# Sheet1.net
KiCad netlist of a schematic drawn in Altium Designer
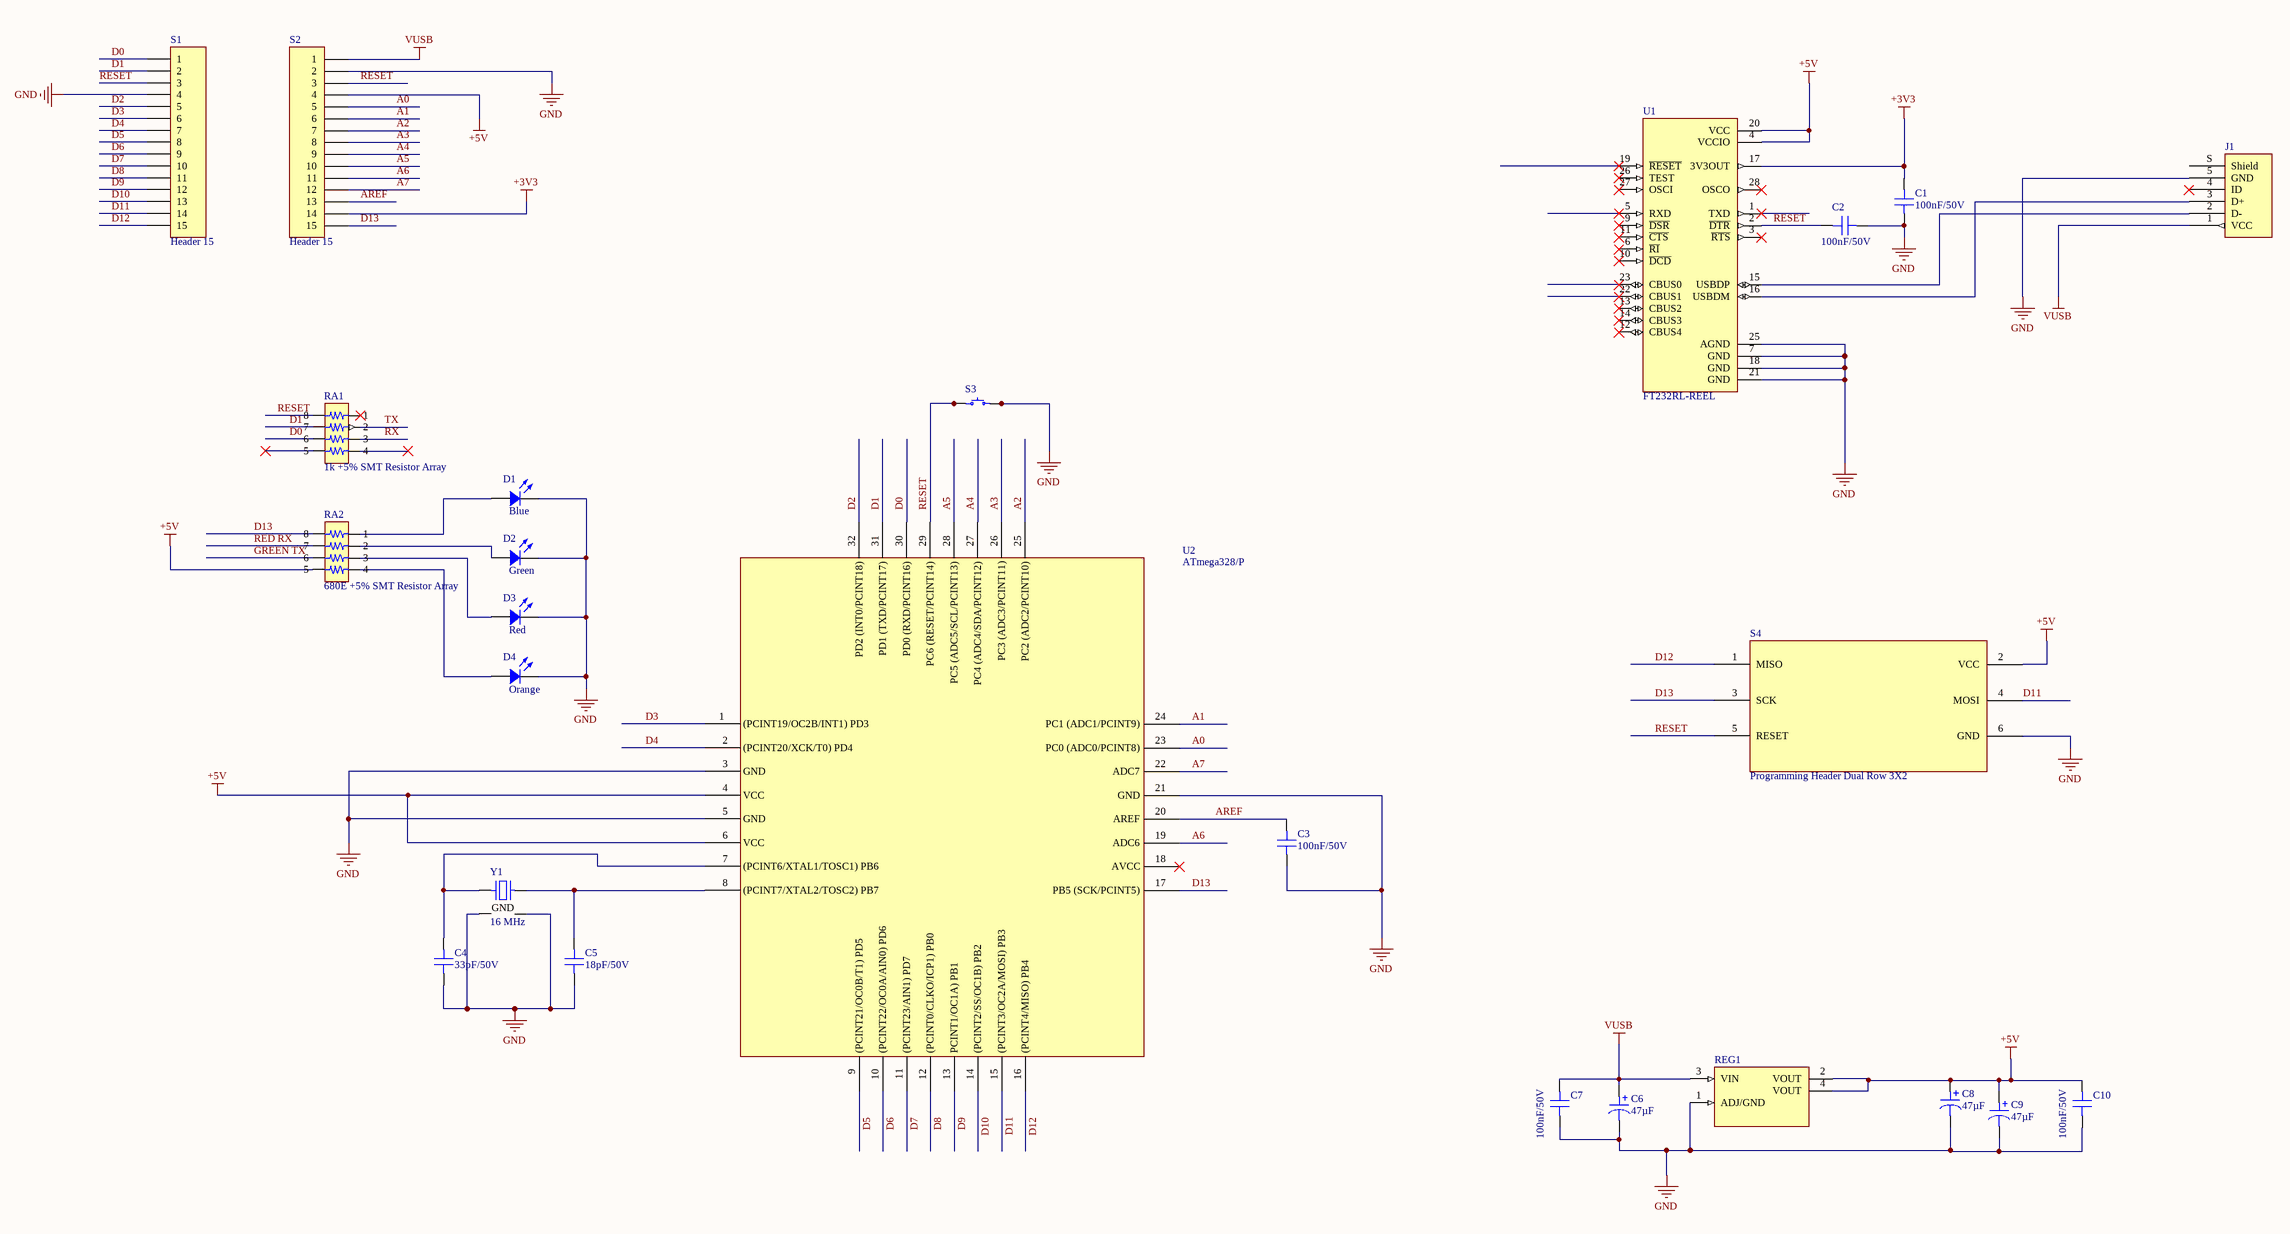
[diagram p0: Sheet1.SchDoc]

(export (version "E")
  (design (tool "Eeschema 10.0.6"))
  (components
    (comp (ref "C1")
      (value "100nF/50V")
      (footprint "CAP 0805_2012")
      (description "CAP CER 0.1UF 50V X5R 0805")
      (fields (field (name "PART NUMBER") "08055D104KAT2A") (field (name "MANUFACTURER") "AVX Corporation"))
      (libsource (lib "Celestial Altium Library - altium_library") (part "Capacitor"))
    )
    (comp (ref "C2")
      (value "100nF/50V")
      (footprint "CAP 0805_2012")
      (description "CAP CER 0.1UF 50V X5R 0805")
      (fields (field (name "PART NUMBER") "08055D104KAT2A") (field (name "MANUFACTURER") "AVX Corporation"))
      (libsource (lib "Celestial Altium Library - altium_library") (part "Capacitor"))
    )
    (comp (ref "C3")
      (value "100nF/50V")
      (footprint "CAP 0805_2012")
      (description "CAP CER 0.1UF 50V X5R 0805")
      (fields (field (name "PART NUMBER") "08055D104KAT2A") (field (name "MANUFACTURER") "AVX Corporation"))
      (libsource (lib "Celestial Altium Library - altium_library") (part "Capacitor"))
    )
    (comp (ref "C4")
      (value "33pF/50V")
      (footprint "CAP 0805_2012")
      (description "CAP CER 18PF 50V C0G/NP0 0805")
      (fields (field (name "PART NUMBER") "08055A180JAT2A") (field (name "MANUFACTURER") "AVX Corporation"))
      (libsource (lib "Celestial Altium Library - altium_library") (part "Capacitor"))
    )
    (comp (ref "C5")
      (value "18pF/50V")
      (footprint "CAP 0805_2012")
      (description "CAP CER 18PF 50V C0G/NP0 0805")
      (fields (field (name "PART NUMBER") "08055A180JAT2A") (field (name "MANUFACTURER") "AVX Corporation"))
      (libsource (lib "Celestial Altium Library - altium_library") (part "Capacitor"))
    )
    (comp (ref "C6")
      (value "47µF")
      (footprint "CAP ALSMD 8.3MM H10.5MM")
      (description "CAP ALUM 47UF 20% 63V SMD")
      (fields (field (name "PART NUMBER") "UUR1J470MNL1GS") (field (name "MANUFACTURER") "Nichicon"))
      (libsource (lib "Celestial Altium Library - altium_library") (part "Polarised Capacitor"))
    )
    (comp (ref "C7")
      (value "100nF/50V")
      (footprint "CAP 0805_2012")
      (description "CAP CER 0.1UF 50V X5R 0805")
      (fields (field (name "PART NUMBER") "08055D104KAT2A") (field (name "MANUFACTURER") "AVX Corporation"))
      (libsource (lib "Celestial Altium Library - altium_library") (part "Capacitor"))
    )
    (comp (ref "C8")
      (value "47µF")
      (footprint "CAP ALSMD 8.3MM H10.5MM")
      (description "CAP ALUM 47UF 20% 35V SMD")
      (fields (field (name "PART NUMBER") "35THV47M8X10.5") (field (name "MANUFACTURER") "Rubycon"))
      (libsource (lib "Celestial Altium Library - altium_library") (part "Polarised Capacitor"))
    )
    (comp (ref "C9")
      (value "47µF")
      (footprint "CAP ALSMD 8.3MM H10.5MM")
      (description "CAP ALUM 47UF 20% 35V SMD")
      (fields (field (name "PART NUMBER") "35THV47M8X10.5") (field (name "MANUFACTURER") "Rubycon"))
      (libsource (lib "Celestial Altium Library - altium_library") (part "Polarised Capacitor"))
    )
    (comp (ref "C10")
      (value "100nF/50V")
      (footprint "CAP 0805_2012")
      (description "CAP CER 0.1UF 50V X5R 0805")
      (fields (field (name "PART NUMBER") "08055D104KAT2A") (field (name "MANUFACTURER") "AVX Corporation"))
      (libsource (lib "Celestial Altium Library - altium_library") (part "Capacitor"))
    )
    (comp (ref "D1")
      (value "Blue")
      (footprint "LED 1206_3216 BLUE")
      (description "LED BLUE CLEAR CHIP SMD")
      (fields (field (name "PART NUMBER") "APT3216QBC/D") (field (name "MANUFACTURER") "Kingbright"))
      (libsource (lib "Celestial Altium Library - altium_library") (part "LED"))
    )
    (comp (ref "D2")
      (value "Green")
      (footprint "LED 1206_3216 GREEN")
      (description "LED GREEN 1206 SMD")
      (fields (field (name "PART NUMBER") "5976325607F") (field (name "MANUFACTURER") "Dialight"))
      (libsource (lib "Celestial Altium Library - altium_library") (part "LED"))
    )
    (comp (ref "D3")
      (value "Red")
      (footprint "LED 1206_3216 RED")
      (description "LED RED 1206 SMD")
      (fields (field (name "PART NUMBER") "5990210007F") (field (name "MANUFACTURER") "Dialight"))
      (libsource (lib "Celestial Altium Library - altium_library") (part "LED"))
    )
    (comp (ref "D4")
      (value "Orange")
      (footprint "LED 1206_3216 RED")
      (description "LED RED 1206 SMD")
      (fields (field (name "PART NUMBER") "5990210007F") (field (name "MANUFACTURER") "Dialight"))
      (libsource (lib "Celestial Altium Library - altium_library") (part "LED"))
    )
    (comp (ref "J1")
      (value "10118193-0001LF")
      (footprint "FCI USB 10118193-0001LF")
      (description "CONN RCPT USB2.0 MICRO B SMD R/A")
      (fields (field (name "MANUFACTURER") "Amphenol ICC (FCI)"))
      (libsource (lib "Celestial Altium Library - altium_library") (part "USB 2.0 Type B Micro"))
    )
    (comp (ref "RA1")
      (value "1k +5% SMT Resistor Array")
      (footprint "RESNET 1206-8 CONCAVE")
      (description "RES ARRAY 4 RES 1K OHM 1206")
      (fields (field (name "PART NUMBER") "TC164-JR-071KL") (field (name "MANUFACTURER") "Yageo"))
      (libsource (lib "Celestial Altium Library - altium_library") (part "Resistor Array (4 circuit)"))
    )
    (comp (ref "RA2")
      (value "680E +5% SMT Resistor Array")
      (footprint "RESNET 1206-8 CONVEX")
      (description "RES ARRAY 4 RES 680 OHM 1206")
      (fields (field (name "PART NUMBER") "YC164-JR-07680RL") (field (name "MANUFACTURER") "Yageo"))
      (libsource (lib "") (part "Resistor Array (4 circuit)_1"))
    )
    (comp (ref "REG1")
      (value "LM1117IMPX-5.0")
      (footprint "SOT230P700X180-4N")
      (description "800-mA/5V Linear Voltage Regulator")
      (fields (field (name "MF") "Texas Instruments") (field (name "MP") "LM1117IMPX-5.0/NOPB"))
      (libsource (lib "LM1117IMPX-5.0") (part "LM1117IMPX-5.0"))
    )
    (comp (ref "S1")
      (value "Header 15")
      (footprint "HDR1X15")
      (description "Header, 15-Pin")
      (fields (field (name "PUBLISHER") "Altium Limited"))
      (libsource (lib "") (part "Header 15_1"))
    )
    (comp (ref "S2")
      (value "Header 15")
      (footprint "HDR1X15")
      (description "Header, 15-Pin")
      (fields (field (name "PUBLISHER") "Altium Limited"))
      (libsource (lib "Miscellaneous Connectors") (part "Header 15"))
    )
    (comp (ref "S3")
      (value "PTS810 SJM 250 SMTR LFS")
      (footprint "C&K PTS810")
      (description "SWITCH TACTILE SPST-NO 0.05A 16V")
      (fields (field (name "MANUFACTURER") "C&K"))
      (libsource (lib "Celestial Altium Library - altium_library") (part "SPST-NO 4 PIN"))
    )
    (comp (ref "S4")
      (value "Programming Header Dual Row 3X2")
      (footprint "Header 3X2")
      (libsource (lib "Schlib1") (part "Header 3X2"))
    )
    (comp (ref "U1")
      (value "FT232RL-REEL")
      (footprint "SOP65P780X200-28N")
      (description "USB Bridge, USB to UART USB 2.0 UART Interface 28-SSOP")
      (fields (field (name "MF") "FTDI,"))
      (libsource (lib "FT232RL-REEL") (part "FT232RL-REEL"))
    )
    (comp (ref "U2")
      (value "ATmega328/P")
      (footprint "TQFP80P900X900X120-32N")
      (libsource (lib "Atmega328p") (part "ATmega328/P"))
    )
    (comp (ref "Y1")
      (value "16 MHz")
      (footprint "NDK NX2520SA")
      (description "CRYSTAL 16.0000MHZ 8PF SMD")
      (fields
        (field (name "PART NUMBER") "NX2520SA-16.000000MHZ-W1")
        (field (name "MANUFACTURER") "NDK America, Inc.")
      )
      (libsource (lib "Celestial Altium Library - altium_library") (part "NDK Crystal NX2520SA"))
    )
  )
  (nets
    (net (code "1") (name "+3V3") (class "Default")
      (node (ref "C1") (pin "2") (pinfunction "2_2") (pintype "passive"))
      (node (ref "S2") (pin "14") (pinfunction "14_14") (pintype "passive"))
      (node (ref "U1") (pin "17") (pinfunction "3V3OUT_17") (pintype "output"))
    )
    (net (code "2") (name "+5V") (class "Default")
      (node (ref "C10") (pin "1") (pinfunction "1_1") (pintype "passive"))
      (node (ref "C8") (pin "1") (pinfunction "1_1") (pintype "passive"))
      (node (ref "C9") (pin "1") (pinfunction "1_1") (pintype "passive"))
      (node (ref "RA2") (pin "4") (pinfunction "4_4") (pintype "passive"))
      (node (ref "REG1") (pin "2") (pinfunction "VOUT_2") (pintype "passive"))
      (node (ref "REG1") (pin "4") (pinfunction "VOUT_4") (pintype "passive"))
      (node (ref "S2") (pin "4") (pinfunction "4_4") (pintype "passive"))
      (node (ref "S4") (pin "2") (pinfunction "VCC_2") (pintype "passive"))
      (node (ref "U1") (pin "20") (pinfunction "VCC_20") (pintype "power_in"))
      (node (ref "U1") (pin "4") (pinfunction "VCCIO_4") (pintype "power_in"))
      (node (ref "U2") (pin "4") (pinfunction "VCC_4") (pintype "passive"))
      (node (ref "U2") (pin "6") (pinfunction "VCC_6") (pintype "passive"))
    )
    (net (code "4") (name "/A0") (class "Default")
      (node (ref "S2") (pin "5") (pinfunction "5_5") (pintype "passive"))
      (node (ref "U2") (pin "23") (pinfunction "PC0_(ADC0/PCINT8)_23") (pintype "passive"))
    )
    (net (code "5") (name "/A1") (class "Default")
      (node (ref "S2") (pin "6") (pinfunction "6_6") (pintype "passive"))
      (node (ref "U2") (pin "24") (pinfunction "PC1_(ADC1/PCINT9)_24") (pintype "passive"))
    )
    (net (code "6") (name "/A2") (class "Default")
      (node (ref "S2") (pin "7") (pinfunction "7_7") (pintype "passive"))
      (node (ref "U2") (pin "25") (pinfunction "PC2_(ADC2/PCINT10)_25") (pintype "passive"))
    )
    (net (code "7") (name "/A3") (class "Default")
      (node (ref "S2") (pin "8") (pinfunction "8_8") (pintype "passive"))
      (node (ref "U2") (pin "26") (pinfunction "PC3_(ADC3/PCINT11)_26") (pintype "passive"))
    )
    (net (code "8") (name "/A4") (class "Default")
      (node (ref "S2") (pin "9") (pinfunction "9_9") (pintype "passive"))
      (node (ref "U2") (pin "27") (pinfunction "PC4_(ADC4/SDA/PCINT12)_27") (pintype "passive"))
    )
    (net (code "9") (name "/A5") (class "Default")
      (node (ref "S2") (pin "10") (pinfunction "10_10") (pintype "passive"))
      (node (ref "U2") (pin "28") (pinfunction "PC5_(ADC5/SCL/PCINT13)_28") (pintype "passive"))
    )
    (net (code "10") (name "/A6") (class "Default")
      (node (ref "S2") (pin "11") (pinfunction "11_11") (pintype "passive"))
      (node (ref "U2") (pin "19") (pinfunction "ADC6_19") (pintype "passive"))
    )
    (net (code "11") (name "/A7") (class "Default")
      (node (ref "S2") (pin "12") (pinfunction "12_12") (pintype "passive"))
      (node (ref "U2") (pin "22") (pinfunction "ADC7_22") (pintype "passive"))
    )
    (net (code "12") (name "/AREF") (class "Default")
      (node (ref "C3") (pin "2") (pinfunction "2_2") (pintype "passive"))
      (node (ref "S2") (pin "13") (pinfunction "13_13") (pintype "passive"))
      (node (ref "U2") (pin "20") (pinfunction "AREF_20") (pintype "passive"))
    )
    (net (code "13") (name "/D0") (class "Default")
      (node (ref "RA1") (pin "3") (pinfunction "3_3") (pintype "passive"))
      (node (ref "S1") (pin "1") (pinfunction "1_1") (pintype "passive"))
      (node (ref "U2") (pin "30") (pinfunction "PD0_(RXD/PCINT16)_30") (pintype "passive"))
    )
    (net (code "14") (name "/D1") (class "Default")
      (node (ref "RA1") (pin "2") (pinfunction "2_2") (pintype "passive"))
      (node (ref "S1") (pin "2") (pinfunction "2_2") (pintype "passive"))
      (node (ref "U2") (pin "31") (pinfunction "PD1_(TXD/PCINT17)_31") (pintype "passive"))
    )
    (net (code "15") (name "/D2") (class "Default")
      (node (ref "S1") (pin "5") (pinfunction "5_5") (pintype "passive"))
      (node (ref "U2") (pin "32") (pinfunction "PD2_(INT0/PCINT18)_32") (pintype "passive"))
    )
    (net (code "16") (name "/D3") (class "Default")
      (node (ref "S1") (pin "6") (pinfunction "6_6") (pintype "passive"))
      (node (ref "U2") (pin "1") (pinfunction "(PCINT19/OC2B/INT1)_PD3_1") (pintype "passive"))
    )
    (net (code "17") (name "/D4") (class "Default")
      (node (ref "S1") (pin "7") (pinfunction "7_7") (pintype "passive"))
      (node (ref "U2") (pin "2") (pinfunction "(PCINT20/XCK/T0)_PD4_2") (pintype "passive"))
    )
    (net (code "18") (name "/D5") (class "Default")
      (node (ref "S1") (pin "8") (pinfunction "8_8") (pintype "passive"))
      (node (ref "U2") (pin "9") (pinfunction "(PCINT21/OC0B/T1)_PD5_9") (pintype "passive"))
    )
    (net (code "19") (name "/D6") (class "Default")
      (node (ref "S1") (pin "9") (pinfunction "9_9") (pintype "passive"))
      (node (ref "U2") (pin "10") (pinfunction "(PCINT22/OC0A/AIN0)_PD6_10") (pintype "passive"))
    )
    (net (code "20") (name "/D7") (class "Default")
      (node (ref "S1") (pin "10") (pinfunction "10_10") (pintype "passive"))
      (node (ref "U2") (pin "11") (pinfunction "(PCINT23/AIN1)_PD7_11") (pintype "passive"))
    )
    (net (code "21") (name "/D8") (class "Default")
      (node (ref "S1") (pin "11") (pinfunction "11_11") (pintype "passive"))
      (node (ref "U2") (pin "12") (pinfunction "(PCINT0/CLKO/ICP1)_PB0_12") (pintype "passive"))
    )
    (net (code "22") (name "/D9") (class "Default")
      (node (ref "S1") (pin "12") (pinfunction "12_12") (pintype "passive"))
      (node (ref "U2") (pin "13") (pinfunction "PCINT1/OC1A)_PB1_13") (pintype "passive"))
    )
    (net (code "23") (name "/D10") (class "Default")
      (node (ref "S1") (pin "13") (pinfunction "13_13") (pintype "passive"))
      (node (ref "U2") (pin "14") (pinfunction "(PCINT2/SS/OC1B)_PB2_14") (pintype "passive"))
    )
    (net (code "24") (name "/D11") (class "Default")
      (node (ref "S1") (pin "14") (pinfunction "14_14") (pintype "passive"))
      (node (ref "S4") (pin "4") (pinfunction "MOSI_4") (pintype "passive"))
      (node (ref "U2") (pin "15") (pinfunction "(PCINT3/OC2A/MOSI)_PB3_15") (pintype "passive"))
    )
    (net (code "25") (name "/D12") (class "Default")
      (node (ref "S1") (pin "15") (pinfunction "15_15") (pintype "passive"))
      (node (ref "S4") (pin "1") (pinfunction "MISO_1") (pintype "passive"))
      (node (ref "U2") (pin "16") (pinfunction "(PCINT4/MISO)_PB4_16") (pintype "passive"))
    )
    (net (code "26") (name "/D13") (class "Default")
      (node (ref "RA2") (pin "1") (pinfunction "1_1") (pintype "passive"))
      (node (ref "S2") (pin "15") (pinfunction "15_15") (pintype "passive"))
      (node (ref "S4") (pin "3") (pinfunction "SCK_3") (pintype "passive"))
      (node (ref "U2") (pin "17") (pinfunction "PB5_(SCK/PCINT5)_17") (pintype "passive"))
    )
    (net (code "27") (name "/GREEN TX") (class "Default")
      (node (ref "RA2") (pin "3") (pinfunction "3_3") (pintype "passive"))
    )
    (net (code "28") (name "/RED RX") (class "Default")
      (node (ref "RA2") (pin "2") (pinfunction "2_2") (pintype "passive"))
    )
    (net (code "29") (name "/RESET") (class "Default")
      (node (ref "C2") (pin "1") (pinfunction "1_1") (pintype "passive"))
      (node (ref "RA1") (pin "1") (pinfunction "1_1") (pintype "passive"))
      (node (ref "S1") (pin "3") (pinfunction "3_3") (pintype "passive"))
      (node (ref "S2") (pin "3") (pinfunction "3_3") (pintype "passive"))
      (node (ref "S3") (pin "1") (pinfunction "1_1") (pintype "passive"))
      (node (ref "S3") (pin "2") (pinfunction "2_2") (pintype "passive"))
      (node (ref "S4") (pin "5") (pinfunction "RESET_5") (pintype "passive"))
      (node (ref "U1") (pin "2") (pinfunction "~{DTR}_2") (pintype "output"))
      (node (ref "U2") (pin "29") (pinfunction "PC6_(RESET/PCINT14)_29") (pintype "passive"))
    )
    (net (code "30") (name "/RX") (class "Default")
      (node (ref "RA1") (pin "6") (pinfunction "6_6") (pintype "passive"))
    )
    (net (code "31") (name "/TX") (class "Default")
      (node (ref "RA1") (pin "7") (pinfunction "7_7") (pintype "output"))
    )
    (net (code "32") (name "GND") (class "Default")
      (node (ref "C1") (pin "1") (pinfunction "1_1") (pintype "passive"))
      (node (ref "C10") (pin "2") (pinfunction "2_2") (pintype "passive"))
      (node (ref "C2") (pin "2") (pinfunction "2_2") (pintype "passive"))
      (node (ref "C3") (pin "1") (pinfunction "1_1") (pintype "passive"))
      (node (ref "C4") (pin "1") (pinfunction "1_1") (pintype "passive"))
      (node (ref "C5") (pin "1") (pinfunction "1_1") (pintype "passive"))
      (node (ref "C6") (pin "2") (pinfunction "2_2") (pintype "passive"))
      (node (ref "C7") (pin "2") (pinfunction "2_2") (pintype "passive"))
      (node (ref "C8") (pin "2") (pinfunction "2_2") (pintype "passive"))
      (node (ref "C9") (pin "2") (pinfunction "2_2") (pintype "passive"))
      (node (ref "D1") (pin "2") (pinfunction "2_2") (pintype "passive"))
      (node (ref "D2") (pin "2") (pinfunction "2_2") (pintype "passive"))
      (node (ref "D3") (pin "2") (pinfunction "2_2") (pintype "passive"))
      (node (ref "D4") (pin "2") (pinfunction "2_2") (pintype "passive"))
      (node (ref "J1") (pin "5") (pinfunction "GND_5") (pintype "passive"))
      (node (ref "REG1") (pin "1") (pinfunction "ADJ/GND_1") (pintype "input"))
      (node (ref "S1") (pin "4") (pinfunction "4_4") (pintype "passive"))
      (node (ref "S2") (pin "2") (pinfunction "2_2") (pintype "passive"))
      (node (ref "S3") (pin "3") (pinfunction "3_3") (pintype "passive"))
      (node (ref "S3") (pin "4") (pinfunction "4_4") (pintype "passive"))
      (node (ref "S4") (pin "6") (pinfunction "GND_6") (pintype "passive"))
      (node (ref "U1") (pin "18") (pinfunction "GND_18") (pintype "power_in"))
      (node (ref "U1") (pin "21") (pinfunction "GND_21") (pintype "power_in"))
      (node (ref "U1") (pin "25") (pinfunction "AGND_25") (pintype "power_in"))
      (node (ref "U1") (pin "7") (pinfunction "GND_7") (pintype "power_in"))
      (node (ref "U2") (pin "21") (pinfunction "GND_21") (pintype "passive"))
      (node (ref "U2") (pin "3") (pinfunction "GND_3") (pintype "passive"))
      (node (ref "U2") (pin "5") (pinfunction "GND_5") (pintype "passive"))
      (node (ref "Y1") (pin "2") (pinfunction "GND_2") (pintype "passive"))
      (node (ref "Y1") (pin "4") (pinfunction "GND_4") (pintype "passive"))
    )
    (net (code "33") (name "Net-(D1-Pad1)") (class "Default")
      (node (ref "D1") (pin "1") (pinfunction "1_1") (pintype "passive"))
      (node (ref "RA2") (pin "8") (pinfunction "8_8") (pintype "passive"))
    )
    (net (code "34") (name "Net-(D2-Pad1)") (class "Default")
      (node (ref "D2") (pin "1") (pinfunction "1_1") (pintype "passive"))
      (node (ref "RA2") (pin "7") (pinfunction "7_7") (pintype "passive"))
    )
    (net (code "35") (name "Net-(D3-Pad1)") (class "Default")
      (node (ref "D3") (pin "1") (pinfunction "1_1") (pintype "passive"))
      (node (ref "RA2") (pin "6") (pinfunction "6_6") (pintype "passive"))
    )
    (net (code "36") (name "Net-(D4-Pad1)") (class "Default")
      (node (ref "D4") (pin "1") (pinfunction "1_1") (pintype "passive"))
      (node (ref "RA2") (pin "5") (pinfunction "5_5") (pintype "passive"))
    )
    (net (code "37") (name "Net-(J1-D+)") (class "Default")
      (node (ref "J1") (pin "3") (pinfunction "D+_3") (pintype "passive"))
      (node (ref "U1") (pin "16") (pinfunction "USBDM_16") (pintype "bidirectional"))
    )
    (net (code "38") (name "Net-(J1-D-)") (class "Default")
      (node (ref "J1") (pin "2") (pinfunction "D-_2") (pintype "passive"))
      (node (ref "U1") (pin "15") (pinfunction "USBDP_15") (pintype "bidirectional"))
    )
    (net (code "39") (name "Net-(U2-(PCINT6{slash}XTAL1{slash}TOSC1)_PB6)") (class "Default")
      (node (ref "C4") (pin "2") (pinfunction "2_2") (pintype "passive"))
      (node (ref "U2") (pin "7") (pinfunction "(PCINT6/XTAL1/TOSC1)_PB6_7") (pintype "passive"))
      (node (ref "Y1") (pin "1") (pinfunction "1_1") (pintype "passive"))
    )
    (net (code "40") (name "Net-(U2-(PCINT7{slash}XTAL2{slash}TOSC2)_PB7)") (class "Default")
      (node (ref "C5") (pin "2") (pinfunction "2_2") (pintype "passive"))
      (node (ref "U2") (pin "8") (pinfunction "(PCINT7/XTAL2/TOSC2)_PB7_8") (pintype "passive"))
      (node (ref "Y1") (pin "3") (pinfunction "3_3") (pintype "passive"))
    )
    (net (code "41") (name "VUSB") (class "Default")
      (node (ref "C6") (pin "1") (pinfunction "1_1") (pintype "passive"))
      (node (ref "C7") (pin "1") (pinfunction "1_1") (pintype "passive"))
      (node (ref "J1") (pin "1") (pinfunction "VCC_1") (pintype "output"))
      (node (ref "REG1") (pin "3") (pinfunction "VIN_3") (pintype "input"))
      (node (ref "S2") (pin "1") (pinfunction "1_1") (pintype "passive"))
    )
    (net (code "42") (name "unconnected-(J1-ID-Pad4)") (class "Default")
      (node (ref "J1") (pin "4") (pinfunction "ID_4") (pintype "passive+no_connect"))
    )
    (net (code "43") (name "unconnected-(J1-Shield-PadS)") (class "Default")
      (node (ref "J1") (pin "S") (pinfunction "Shield_S") (pintype "passive"))
    )
    (net (code "44") (name "unconnected-(RA1-8-Pad)") (class "Default")
      (node (ref "RA1") (pin "") (pinfunction "8_") (pintype "passive+no_connect"))
    )
    (net (code "45") (name "unconnected-(RA1-Pad4)") (class "Default")
      (node (ref "RA1") (pin "4") (pinfunction "4_4") (pintype "passive+no_connect"))
    )
    (net (code "46") (name "unconnected-(RA1-Pad5)") (class "Default")
      (node (ref "RA1") (pin "5") (pinfunction "5_5") (pintype "passive+no_connect"))
    )
    (net (code "47") (name "unconnected-(U1-CBUS0-Pad23)") (class "Default")
      (node (ref "U1") (pin "23") (pinfunction "CBUS0_23") (pintype "bidirectional+no_connect"))
    )
    (net (code "48") (name "unconnected-(U1-CBUS1-Pad22)") (class "Default")
      (node (ref "U1") (pin "22") (pinfunction "CBUS1_22") (pintype "bidirectional+no_connect"))
    )
    (net (code "49") (name "unconnected-(U1-CBUS2-Pad13)") (class "Default")
      (node (ref "U1") (pin "13") (pinfunction "CBUS2_13") (pintype "bidirectional+no_connect"))
    )
    (net (code "50") (name "unconnected-(U1-CBUS3-Pad14)") (class "Default")
      (node (ref "U1") (pin "14") (pinfunction "CBUS3_14") (pintype "bidirectional+no_connect"))
    )
    (net (code "51") (name "unconnected-(U1-CBUS4-Pad12)") (class "Default")
      (node (ref "U1") (pin "12") (pinfunction "CBUS4_12") (pintype "bidirectional+no_connect"))
    )
    (net (code "52") (name "unconnected-(U1-OSCI-Pad27)") (class "Default")
      (node (ref "U1") (pin "27") (pinfunction "OSCI_27") (pintype "input+no_connect"))
    )
    (net (code "53") (name "unconnected-(U1-OSCO-Pad28)") (class "Default")
      (node (ref "U1") (pin "28") (pinfunction "OSCO_28") (pintype "output+no_connect"))
    )
    (net (code "54") (name "unconnected-(U1-RXD-Pad5)") (class "Default")
      (node (ref "U1") (pin "5") (pinfunction "RXD_5") (pintype "input+no_connect"))
    )
    (net (code "55") (name "unconnected-(U1-TEST-Pad26)") (class "Default")
      (node (ref "U1") (pin "26") (pinfunction "TEST_26") (pintype "input+no_connect"))
    )
    (net (code "56") (name "unconnected-(U1-TXD-Pad1)") (class "Default")
      (node (ref "U1") (pin "1") (pinfunction "TXD_1") (pintype "output+no_connect"))
    )
    (net (code "57") (name "unconnected-(U1-~{CTS}-Pad11)") (class "Default")
      (node (ref "U1") (pin "11") (pinfunction "~{CTS}_11") (pintype "input+no_connect"))
    )
    (net (code "58") (name "unconnected-(U1-~{DCD}-Pad10)") (class "Default")
      (node (ref "U1") (pin "10") (pinfunction "~{DCD}_10") (pintype "input+no_connect"))
    )
    (net (code "59") (name "unconnected-(U1-~{DSR}-Pad9)") (class "Default")
      (node (ref "U1") (pin "9") (pinfunction "~{DSR}_9") (pintype "input+no_connect"))
    )
    (net (code "60") (name "unconnected-(U1-~{RESET}-Pad19)") (class "Default")
      (node (ref "U1") (pin "19") (pinfunction "~{RESET}_19") (pintype "input+no_connect"))
    )
    (net (code "61") (name "unconnected-(U1-~{RI}-Pad6)") (class "Default")
      (node (ref "U1") (pin "6") (pinfunction "~{RI}_6") (pintype "input+no_connect"))
    )
    (net (code "62") (name "unconnected-(U1-~{RTS}-Pad3)") (class "Default")
      (node (ref "U1") (pin "3") (pinfunction "~{RTS}_3") (pintype "output+no_connect"))
    )
    (net (code "63") (name "unconnected-(U2-AVCC-Pad18)") (class "Default")
      (node (ref "U2") (pin "18") (pinfunction "AVCC_18") (pintype "passive+no_connect"))
    )
  )
)
